# NFC_Access_Pwr_R00.net
KiCad netlist of a schematic drawn in Altium Designer
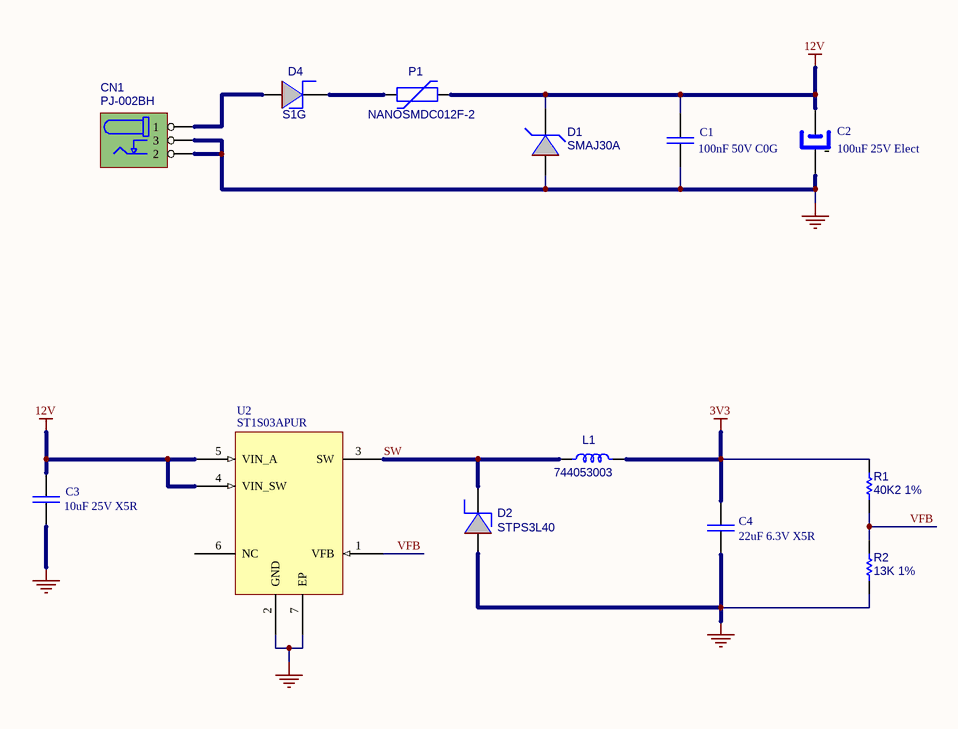
[diagram p0: NFC_Access_Pwr_R00.SchDoc]

(export (version "E")
  (design (tool "Eeschema 10.0.6"))
  (components
    (comp (ref "C1")
      (value "100nF 50V C0G")
      (footprint "C_1206")
      (description "Ceramic Capacitor\r\nMNF: GRM31C5C1H104JA01L\r\nDGK: 490-6505-2-ND")
      (libsource (lib "NFC_Access_Lib") (part "Ceramic capacitor"))
    )
    (comp (ref "C2")
      (value "100uF 25V Elect")
      (footprint "CAP_ELECT_6.3_7.7")
      (description "Polarized Capacitor\r\n732-8438-2-ND")
      (libsource (lib "NFC_Access_Lib") (part "Pol capacitor"))
    )
    (comp (ref "C3")
      (value "10uF 25V X5R")
      (footprint "C_1206")
      (description "Ceramic Capacitor\r\nMNF:GRM31CR61E106KA12L\r\nDGK:490-3373-2-ND")
      (libsource (lib "NFC_Access_Lib") (part "Ceramic capacitor"))
    )
    (comp (ref "C4")
      (value "22uF 6.3V X5R")
      (footprint "C_1206")
      (description "Ceramic Capacitor\r\nMNF: GRM31CR60J226KE19L\r\nDGK: 490-1824-2-ND")
      (libsource (lib "NFC_Access_Lib") (part "Ceramic capacitor"))
    )
    (comp (ref "CN1")
      (value "PJ-002BH")
      (footprint "PJ002B")
      (description "Barrel Power Connector\r\nCP-002BH-ND")
      (libsource (lib "NFC_Access_Lib") (part "CN_PowerJack"))
    )
    (comp (ref "D1")
      (value "SMAJ30A")
      (footprint "D_SMA")
      (description "Unidirectional TVS\r\nSMAJ30ABTR-ND")
      (libsource (lib "NFC_Access_Lib") (part "DIODE_TVS"))
    )
    (comp (ref "D2")
      (value "STPS3L40")
      (footprint "D_214")
      (description "Diode Shottky\r\n497-4673-2-ND")
      (libsource (lib "NFC_Access_Lib") (part "DIODO_SH"))
    )
    (comp (ref "D4")
      (value "S1G")
      (footprint "D_SMA")
      (description "Diode Shottky\r\n1655-S1GTR-ND")
      (libsource (lib "") (part "DIODO_SH_1"))
    )
    (comp (ref "L1")
      (value "744053003")
      (footprint "744053003")
      (description "FIXED IND 3UH 2.8A 30 MOHM SMD\r\n732-1037-2-ND")
      (libsource (lib "NFC_Access_Lib") (part "IND"))
    )
    (comp (ref "P1")
      (value "NANOSMDC012F-2")
      (footprint "NANOSMDC")
      (description "Polyswitch\r\nNANOSMDC012F-2TR-ND")
      (libsource (lib "NFC_Access_Lib") (part "PLYSW"))
    )
    (comp (ref "R1")
      (value "40K2 1%")
      (footprint "R_0603")
      (description "Resistor\r\nCR0603-FX-4022ELFTR-ND")
      (libsource (lib "NFC_Access_Lib") (part "Res1"))
    )
    (comp (ref "R2")
      (value "13K 1%")
      (footprint "R_0603")
      (description "Resistor\r\nCR0603-FX-1302ELFTR-ND")
      (libsource (lib "NFC_Access_Lib") (part "Res1"))
    )
    (comp (ref "U2")
      (value "ST1S03APUR")
      (footprint "6-VDFN")
      (description "IC REG BUCK ADJUSTABLE 1.5A\r\n497-6902-2-ND")
      (libsource (lib "NFC_Access_Lib") (part "ST1S03"))
    )
  )
  (nets
    (net (code "1") (name "/SW") (class "Default")
      (node (ref "D2") (pin "2") (pinfunction "K_2") (pintype "passive"))
      (node (ref "L1") (pin "1") (pinfunction "1_1") (pintype "passive"))
      (node (ref "U2") (pin "3") (pinfunction "SW_3") (pintype "power_in"))
    )
    (net (code "2") (name "/VFB") (class "Default")
      (node (ref "R1") (pin "1") (pinfunction "1_1") (pintype "passive"))
      (node (ref "R2") (pin "2") (pinfunction "2_2") (pintype "passive"))
      (node (ref "U2") (pin "1") (pinfunction "VFB_1") (pintype "input"))
    )
    (net (code "3") (name "3V3") (class "Default")
      (node (ref "C4") (pin "1") (pinfunction "1_1") (pintype "passive"))
      (node (ref "L1") (pin "2") (pinfunction "2_2") (pintype "passive"))
      (node (ref "R1") (pin "2") (pinfunction "2_2") (pintype "passive"))
    )
    (net (code "4") (name "12V") (class "Default")
      (node (ref "C1") (pin "1") (pinfunction "1_1") (pintype "passive"))
      (node (ref "C2") (pin "1") (pinfunction "1_1") (pintype "passive"))
      (node (ref "C3") (pin "1") (pinfunction "1_1") (pintype "passive"))
      (node (ref "D1") (pin "2") (pinfunction "K_2") (pintype "passive"))
      (node (ref "P1") (pin "2") (pinfunction "2_2") (pintype "passive"))
      (node (ref "U2") (pin "4") (pinfunction "VIN_SW_4") (pintype "input"))
      (node (ref "U2") (pin "5") (pinfunction "VIN_A_5") (pintype "input"))
    )
    (net (code "5") (name "GND") (class "Default")
      (node (ref "C1") (pin "2") (pinfunction "2_2") (pintype "passive"))
      (node (ref "C2") (pin "2") (pinfunction "2_2") (pintype "passive"))
      (node (ref "C3") (pin "2") (pinfunction "2_2") (pintype "passive"))
      (node (ref "C4") (pin "2") (pinfunction "2_2") (pintype "passive"))
      (node (ref "CN1") (pin "2") (pinfunction "2_2") (pintype "power_in"))
      (node (ref "CN1") (pin "3") (pinfunction "3_3") (pintype "power_in"))
      (node (ref "D1") (pin "1") (pinfunction "A_1") (pintype "passive"))
      (node (ref "D2") (pin "1") (pinfunction "A_1") (pintype "passive"))
      (node (ref "R2") (pin "1") (pinfunction "1_1") (pintype "passive"))
      (node (ref "U2") (pin "2") (pinfunction "GND_2") (pintype "power_in"))
      (node (ref "U2") (pin "7") (pinfunction "EP_7") (pintype "power_in"))
    )
    (net (code "6") (name "Net-(D4-A)") (class "Default")
      (node (ref "CN1") (pin "1") (pinfunction "1_1") (pintype "power_in"))
      (node (ref "D4") (pin "1") (pinfunction "A_1") (pintype "passive"))
    )
    (net (code "7") (name "Net-(D4-K)") (class "Default")
      (node (ref "D4") (pin "2") (pinfunction "K_2") (pintype "passive"))
      (node (ref "P1") (pin "1") (pinfunction "1_1") (pintype "passive"))
    )
    (net (code "8") (name "unconnected-(U2-NC-Pad6)") (class "Default")
      (node (ref "U2") (pin "6") (pinfunction "NC_6") (pintype "passive"))
    )
  )
)
